# Sheet1.net
KiCad netlist of a schematic drawn in Altium Designer
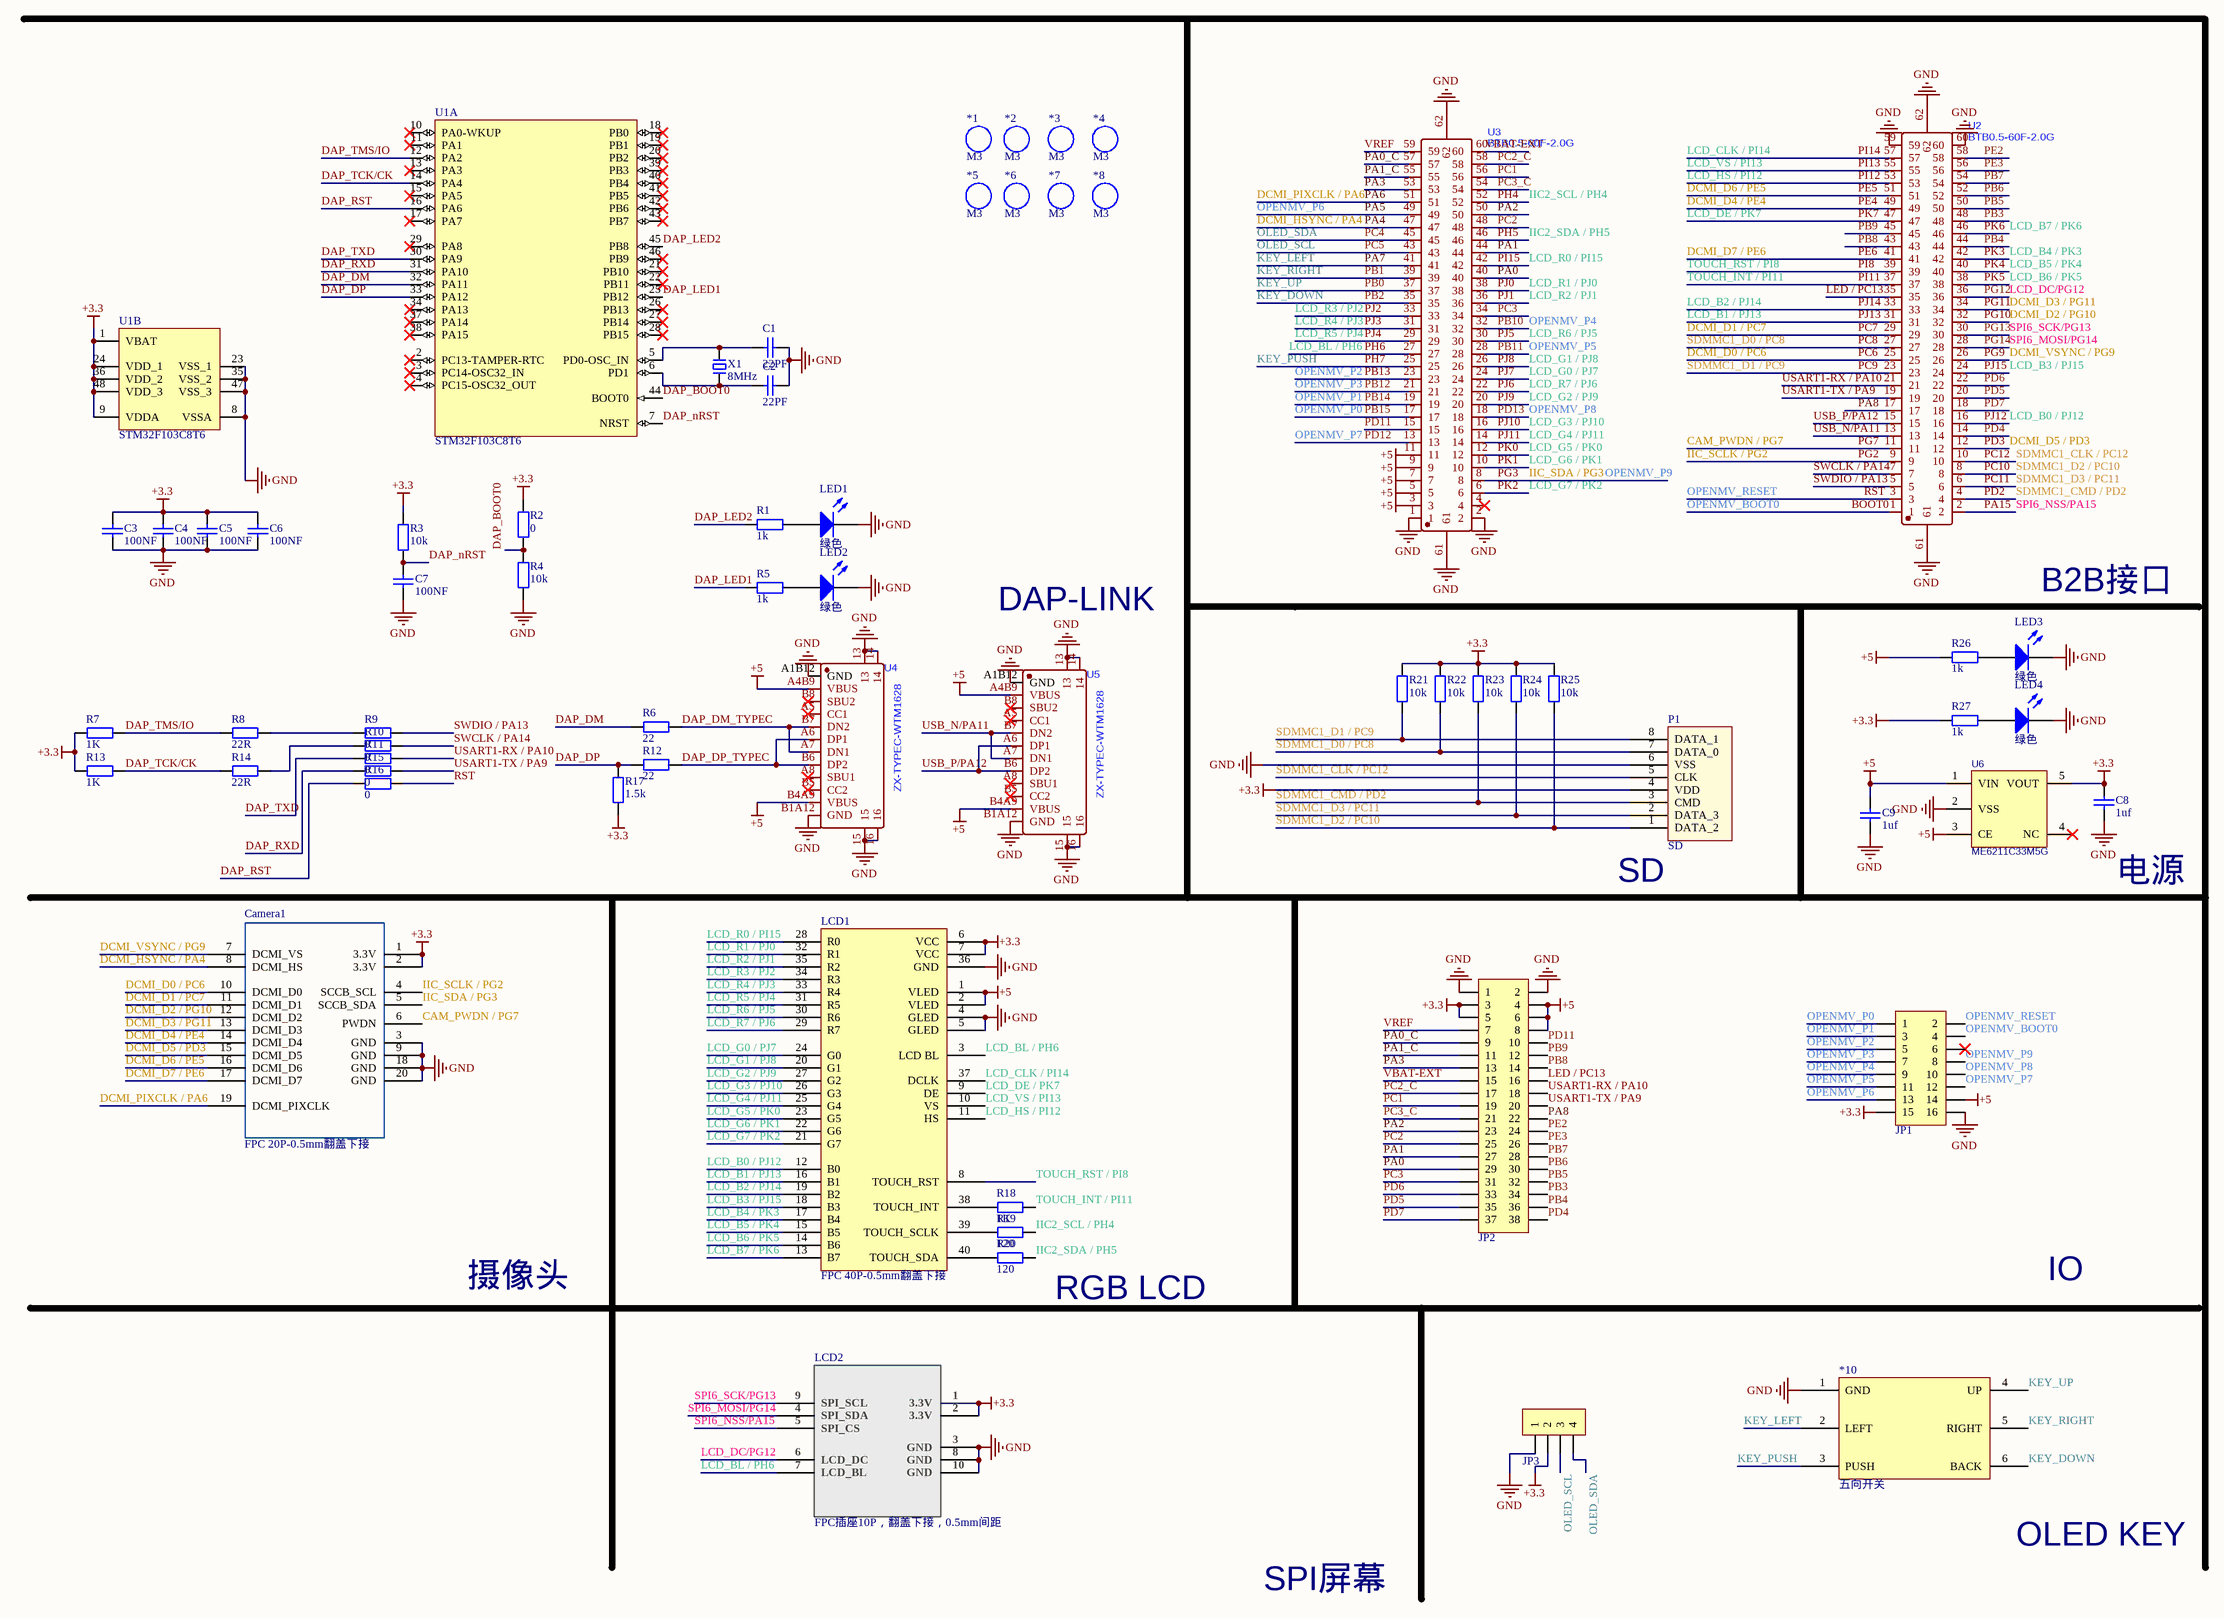
[diagram p0: Sheet1.SchDoc]

(export (version "E")
  (design (tool "Eeschema 10.0.6"))
  (components
    (comp (ref "*1")
      (value "M3")
      (footprint "PCB1:M3 125X200")
      (description "铜柱孔")
      (libsource (lib "STM32H750底板") (part "M3"))
    )
    (comp (ref "*2")
      (value "M3")
      (footprint "PCB1:M3 125X200")
      (description "铜柱孔")
      (libsource (lib "STM32H750底板") (part "M3"))
    )
    (comp (ref "*3")
      (value "M3")
      (footprint "PCB1:M3 125X200")
      (description "铜柱孔")
      (libsource (lib "STM32H750底板") (part "M3"))
    )
    (comp (ref "*4")
      (value "M3")
      (footprint "PCB1:M3 125X200")
      (description "铜柱孔")
      (libsource (lib "STM32H750底板") (part "M3"))
    )
    (comp (ref "*5")
      (value "M3")
      (footprint "PCB1:M3 125X200")
      (description "铜柱孔")
      (libsource (lib "STM32H750底板") (part "M3"))
    )
    (comp (ref "*6")
      (value "M3")
      (footprint "PCB1:M3 125X200")
      (description "铜柱孔")
      (libsource (lib "STM32H750底板") (part "M3"))
    )
    (comp (ref "*7")
      (value "M3")
      (footprint "PCB1:M3 125X200")
      (description "铜柱孔")
      (libsource (lib "STM32H750底板") (part "M3"))
    )
    (comp (ref "*8")
      (value "M3")
      (footprint "PCB1:M3 125X200")
      (description "铜柱孔")
      (libsource (lib "STM32H750底板") (part "M3"))
    )
    (comp (ref "*10")
      (value "五向开关")
      (footprint "PCB1:PCBComponent_1 - duplicate")
      (libsource (lib "STM32H750底板") (part "五向开关"))
    )
    (comp (ref "C1")
      (value "22PF")
      (footprint "PCB1:C0603_L")
      (description "贴片电容/MLCC电容")
      (libsource (lib "STM32H750底板") (part "C"))
    )
    (comp (ref "C2")
      (value "22PF")
      (footprint "PCB1:C0603_L")
      (description "贴片电容/MLCC电容")
      (libsource (lib "STM32H750底板") (part "C"))
    )
    (comp (ref "C3")
      (value "100NF")
      (footprint "PCB1:C0603_L")
      (description "贴片电容/MLCC电容")
      (libsource (lib "STM32H750底板") (part "C"))
    )
    (comp (ref "C4")
      (value "100NF")
      (footprint "PCB1:C0603_L")
      (description "贴片电容/MLCC电容")
      (libsource (lib "STM32H750底板") (part "C"))
    )
    (comp (ref "C5")
      (value "100NF")
      (footprint "PCB1:C0603_L")
      (description "贴片电容/MLCC电容")
      (libsource (lib "STM32H750底板") (part "C"))
    )
    (comp (ref "C6")
      (value "100NF")
      (footprint "PCB1:C0603_L")
      (description "贴片电容/MLCC电容")
      (libsource (lib "STM32H750底板") (part "C"))
    )
    (comp (ref "C7")
      (value "100NF")
      (footprint "PCB1:C0603_L")
      (description "贴片电容/MLCC电容")
      (libsource (lib "STM32H750底板") (part "C"))
    )
    (comp (ref "C8")
      (value "1uf")
      (footprint "PCB1:C0603_L")
      (description "贴片电容/MLCC电容")
      (libsource (lib "STM32H750底板") (part "C"))
    )
    (comp (ref "C9")
      (value "1uf")
      (footprint "PCB1:C0603_L")
      (description "贴片电容/MLCC电容")
      (libsource (lib "STM32H750底板") (part "C"))
    )
    (comp (ref "Camera1")
      (value "FPC 20P-0.5mm翻盖下接")
      (footprint "PCB1:FPC20P-0.5MM")
      (libsource (lib "STM32H750底板") (part "FK_Camera"))
    )
    (comp (ref "JP1")
      (value "Header 8X2")
      (footprint "PCB1:HDR2.54-LI-2x8P")
      (description "8*2P接插件")
      (libsource (lib "STM32H750底板") (part "Header 8X2"))
    )
    (comp (ref "JP2")
      (value "Header 2X11")
      (footprint "PCB1:HDR2.54-LI-2x19P")
      (description "19*2P接插件")
      (libsource (lib "STM32H750底板") (part "Header 19X2"))
    )
    (comp (ref "JP3")
      (value "HDR-1X4")
      (footprint "PCB1:HDR2.54-LI-4P")
      (description "4P接插件")
      (libsource (lib "STM32H750底板") (part "Header 4"))
    )
    (comp (ref "LCD1")
      (value "FPC 40P-0.5mm翻盖下接")
      (footprint "PCB1:FPC40P-0.5MM")
      (libsource (lib "STM32H750底板") (part "MY-RGB"))
    )
    (comp (ref "LCD2")
      (value "FPC插座10P，翻盖下接，0.5mm间距")
      (footprint "PCB1:FPC10P-0.5MM")
      (libsource (lib "STM32H750底板") (part "LCD-SPI"))
    )
    (comp (ref "LED1")
      (value "绿色")
      (footprint "PCB1:LED0805_G")
      (description "贴片LED")
      (libsource (lib "STM32H750底板") (part "LED"))
    )
    (comp (ref "LED2")
      (value "绿色")
      (footprint "PCB1:LED0805_G")
      (description "贴片LED")
      (libsource (lib "STM32H750底板") (part "LED"))
    )
    (comp (ref "LED3")
      (value "绿色")
      (footprint "PCB1:LED0805_G")
      (description "贴片LED")
      (libsource (lib "STM32H750底板") (part "LED"))
    )
    (comp (ref "LED4")
      (value "绿色")
      (footprint "PCB1:LED0805_G")
      (description "贴片LED")
      (libsource (lib "STM32H750底板") (part "LED"))
    )
    (comp (ref "P1")
      (value "SD")
      (footprint "PCB1:MICRO SD")
      (description "自弹式TF卡座")
      (libsource (lib "STM32H750底板") (part "Micro SD_SD"))
    )
    (comp (ref "R1")
      (value "1k")
      (footprint "PCB1:R0603_L")
      (description "贴片电阻")
      (libsource (lib "STM32H750底板") (part "R"))
    )
    (comp (ref "R2")
      (value "0")
      (footprint "PCB1:R0603_L")
      (description "贴片电阻")
      (libsource (lib "STM32H750底板") (part "R"))
    )
    (comp (ref "R3")
      (value "10k")
      (footprint "PCB1:R0603_L")
      (description "贴片电阻")
      (libsource (lib "STM32H750底板") (part "R"))
    )
    (comp (ref "R4")
      (value "10k")
      (footprint "PCB1:R0603_L")
      (description "贴片电阻")
      (libsource (lib "STM32H750底板") (part "R"))
    )
    (comp (ref "R5")
      (value "1k")
      (footprint "PCB1:R0603_L")
      (description "贴片电阻")
      (libsource (lib "STM32H750底板") (part "R"))
    )
    (comp (ref "R6")
      (value "22")
      (footprint "PCB1:R0402_L")
      (description "贴片电阻")
      (libsource (lib "STM32H750底板") (part "R"))
    )
    (comp (ref "R7")
      (value "1K")
      (footprint "PCB1:R0603_L")
      (description "贴片电阻")
      (libsource (lib "STM32H750底板") (part "R"))
    )
    (comp (ref "R8")
      (value "22R")
      (footprint "PCB1:R0603_L")
      (description "贴片电阻")
      (libsource (lib "STM32H750底板") (part "R"))
    )
    (comp (ref "R9")
      (value "0")
      (footprint "PCB1:R0603_L")
      (description "贴片电阻")
      (libsource (lib "STM32H750底板") (part "R"))
    )
    (comp (ref "R10")
      (value "0")
      (footprint "PCB1:R0603_L")
      (description "贴片电阻")
      (libsource (lib "STM32H750底板") (part "R"))
    )
    (comp (ref "R11")
      (value "0")
      (footprint "PCB1:R0603_L")
      (description "贴片电阻")
      (libsource (lib "STM32H750底板") (part "R"))
    )
    (comp (ref "R12")
      (value "22")
      (footprint "PCB1:R0402_L")
      (description "贴片电阻")
      (libsource (lib "STM32H750底板") (part "R"))
    )
    (comp (ref "R13")
      (value "1K")
      (footprint "PCB1:R0603_L")
      (description "贴片电阻")
      (libsource (lib "STM32H750底板") (part "R"))
    )
    (comp (ref "R14")
      (value "22R")
      (footprint "PCB1:R0603_L")
      (description "贴片电阻")
      (libsource (lib "STM32H750底板") (part "R"))
    )
    (comp (ref "R15")
      (value "0")
      (footprint "PCB1:R0603_L")
      (description "贴片电阻")
      (libsource (lib "STM32H750底板") (part "R"))
    )
    (comp (ref "R16")
      (value "0")
      (footprint "PCB1:R0603_L")
      (description "贴片电阻")
      (libsource (lib "STM32H750底板") (part "R"))
    )
    (comp (ref "R17")
      (value "1.5k")
      (footprint "PCB1:R0402_L")
      (description "贴片电阻")
      (libsource (lib "STM32H750底板") (part "R"))
    )
    (comp (ref "R18")
      (value "1K")
      (footprint "PCB1:R0603_L")
      (description "贴片电阻")
      (libsource (lib "STM32H750底板") (part "R"))
    )
    (comp (ref "R19")
      (value "120")
      (footprint "PCB1:R0603_L")
      (description "贴片电阻")
      (libsource (lib "STM32H750底板") (part "R"))
    )
    (comp (ref "R20")
      (value "120")
      (footprint "PCB1:R0603_L")
      (description "贴片电阻")
      (libsource (lib "STM32H750底板") (part "R"))
    )
    (comp (ref "R21")
      (value "10k")
      (footprint "PCB1:R0603_L")
      (description "贴片电阻")
      (libsource (lib "STM32H750底板") (part "R"))
    )
    (comp (ref "R22")
      (value "10k")
      (footprint "PCB1:R0603_L")
      (description "贴片电阻")
      (libsource (lib "STM32H750底板") (part "R"))
    )
    (comp (ref "R23")
      (value "10k")
      (footprint "PCB1:R0603_L")
      (description "贴片电阻")
      (libsource (lib "STM32H750底板") (part "R"))
    )
    (comp (ref "R24")
      (value "10k")
      (footprint "PCB1:R0603_L")
      (description "贴片电阻")
      (libsource (lib "STM32H750底板") (part "R"))
    )
    (comp (ref "R25")
      (value "10k")
      (footprint "PCB1:R0603_L")
      (description "贴片电阻")
      (libsource (lib "STM32H750底板") (part "R"))
    )
    (comp (ref "R26")
      (value "1k")
      (footprint "PCB1:R0603_L")
      (description "贴片电阻")
      (libsource (lib "STM32H750底板") (part "R"))
    )
    (comp (ref "R27")
      (value "1k")
      (footprint "PCB1:R0603_L")
      (description "贴片电阻")
      (libsource (lib "STM32H750底板") (part "R"))
    )
    (comp (ref "U1")
      (value "STM32F103C8T6")
      (footprint "PCB1:LQFP48_N")
      (libsource (lib "STM32H750底板") (part "STM32F103C8T6"))
    )
    (comp (ref "U2")
      (value "BTB0.5-60F-2.0G")
      (footprint "PCB1:CONN-SMD_60P-P0.50_BTB0.5-60F-2.0G")
      (libsource (lib "STM32H750底板") (part "BTB0.5-60F-2.0G"))
    )
    (comp (ref "U3")
      (value "BTB0.5-60F-2.0G")
      (footprint "PCB1:CONN-SMD_60P-P0.50_BTB0.5-60F-2.0G")
      (libsource (lib "STM32H750底板") (part "BTB0.5-60F-2.0G"))
    )
    (comp (ref "U4")
      (value "ZX-TYPEC-WTM1628")
      (footprint "PCB1:USB-C-SMD_ZX-TYPEC-WTM1628")
      (libsource (lib "STM32H750底板") (part "ZX-TYPEC-WTM1628"))
    )
    (comp (ref "U5")
      (value "ZX-TYPEC-WTM1628")
      (footprint "PCB1:USB-C-SMD_ZX-TYPEC-WTM1628")
      (libsource (lib "STM32H750底板") (part "ZX-TYPEC-WTM1628"))
    )
    (comp (ref "U6")
      (value "ME6211C33M5G")
      (footprint "PCB1:SOT-23-5")
      (description "LDO 3.3V/0.5A")
      (libsource (lib "STM32H750底板") (part "ME6211C33"))
    )
    (comp (ref "X1")
      (value "8MHz")
      (footprint "PCB1:XTAL-3215-2P")
      (description "2脚无源晶振(谐振器）")
      (libsource (lib "STM32H750底板") (part "XTAL-2P"))
    )
  )
  (nets
    (net (code "1") (name "+3.3") (class "Default")
      (node (ref "C3") (pin "2") (pinfunction "2_2") (pintype "passive"))
      (node (ref "C4") (pin "2") (pinfunction "2_2") (pintype "passive"))
      (node (ref "C5") (pin "2") (pinfunction "2_2") (pintype "passive"))
      (node (ref "C6") (pin "2") (pinfunction "2_2") (pintype "passive"))
      (node (ref "C8") (pin "2") (pinfunction "2_2") (pintype "passive"))
      (node (ref "Camera1") (pin "1") (pinfunction "3.3V_1") (pintype "passive"))
      (node (ref "Camera1") (pin "2") (pinfunction "3.3V_2") (pintype "passive"))
      (node (ref "JP1") (pin "15") (pinfunction "15_15") (pintype "passive"))
      (node (ref "JP2") (pin "3") (pinfunction "3_3") (pintype "passive"))
      (node (ref "JP2") (pin "5") (pinfunction "5_5") (pintype "passive"))
      (node (ref "JP3") (pin "2") (pinfunction "2_2") (pintype "passive"))
      (node (ref "LCD1") (pin "6") (pinfunction "VCC_6") (pintype "passive"))
      (node (ref "LCD1") (pin "7") (pinfunction "VCC_7") (pintype "passive"))
      (node (ref "LCD2") (pin "1") (pinfunction "3.3V_1") (pintype "passive"))
      (node (ref "LCD2") (pin "2") (pinfunction "3.3V_2") (pintype "passive"))
      (node (ref "P1") (pin "4") (pinfunction "VDD_4") (pintype "passive"))
      (node (ref "R13") (pin "1") (pinfunction "1_1") (pintype "passive"))
      (node (ref "R17") (pin "1") (pinfunction "1_1") (pintype "passive"))
      (node (ref "R2") (pin "2") (pinfunction "2_2") (pintype "passive"))
      (node (ref "R21") (pin "1") (pinfunction "1_1") (pintype "passive"))
      (node (ref "R22") (pin "1") (pinfunction "1_1") (pintype "passive"))
      (node (ref "R23") (pin "1") (pinfunction "1_1") (pintype "passive"))
      (node (ref "R24") (pin "1") (pinfunction "1_1") (pintype "passive"))
      (node (ref "R25") (pin "1") (pinfunction "1_1") (pintype "passive"))
      (node (ref "R27") (pin "1") (pinfunction "1_1") (pintype "passive"))
      (node (ref "R3") (pin "2") (pinfunction "2_2") (pintype "passive"))
      (node (ref "R7") (pin "1") (pinfunction "1_1") (pintype "passive"))
      (node (ref "U1") (pin "1") (pinfunction "VBAT_1") (pintype "power_in"))
      (node (ref "U1") (pin "24") (pinfunction "VDD_1_24") (pintype "power_in"))
      (node (ref "U1") (pin "36") (pinfunction "VDD_2_36") (pintype "power_in"))
      (node (ref "U1") (pin "48") (pinfunction "VDD_3_48") (pintype "power_in"))
      (node (ref "U1") (pin "9") (pinfunction "VDDA_9") (pintype "power_in"))
      (node (ref "U6") (pin "5") (pinfunction "VOUT_5") (pintype "passive"))
    )
    (net (code "2") (name "+5") (class "Default")
      (node (ref "C9") (pin "2") (pinfunction "2_2") (pintype "passive"))
      (node (ref "JP1") (pin "14") (pinfunction "14_14") (pintype "passive"))
      (node (ref "JP2") (pin "4") (pinfunction "4_4") (pintype "passive"))
      (node (ref "JP2") (pin "6") (pinfunction "6_6") (pintype "passive"))
      (node (ref "JP2") (pin "8") (pinfunction "8_8") (pintype "passive"))
      (node (ref "LCD1") (pin "1") (pinfunction "VLED_1") (pintype "passive"))
      (node (ref "LCD1") (pin "2") (pinfunction "VLED_2") (pintype "passive"))
      (node (ref "R26") (pin "1") (pinfunction "1_1") (pintype "passive"))
      (node (ref "U3") (pin "11") (pinfunction "11_11") (pintype "passive"))
      (node (ref "U3") (pin "3") (pinfunction "3_3") (pintype "passive"))
      (node (ref "U3") (pin "5") (pinfunction "5_5") (pintype "passive"))
      (node (ref "U3") (pin "7") (pinfunction "7_7") (pintype "passive"))
      (node (ref "U3") (pin "9") (pinfunction "9_9") (pintype "passive"))
      (node (ref "U4") (pin "A4B9") (pinfunction "VBUS_A4B9") (pintype "passive"))
      (node (ref "U4") (pin "B4A9") (pinfunction "VBUS_B4A9") (pintype "passive"))
      (node (ref "U5") (pin "A4B9") (pinfunction "VBUS_A4B9") (pintype "passive"))
      (node (ref "U5") (pin "B4A9") (pinfunction "VBUS_B4A9") (pintype "passive"))
      (node (ref "U6") (pin "1") (pinfunction "VIN_1") (pintype "passive"))
      (node (ref "U6") (pin "3") (pinfunction "CE_3") (pintype "passive"))
    )
    (net (code "3") (name "/BOOT0") (class "Default")
      (node (ref "JP1") (pin "4") (pinfunction "4_4") (pintype "passive"))
      (node (ref "U2") (pin "1") (pinfunction "1_1") (pintype "passive"))
    )
    (net (code "4") (name "/CAM_PWDN {slash} PG7") (class "Default")
      (node (ref "Camera1") (pin "6") (pinfunction "PWDN_6") (pintype "passive"))
      (node (ref "U2") (pin "11") (pinfunction "11_11") (pintype "passive"))
    )
    (net (code "5") (name "/DAP_BOOT0") (class "Default")
      (node (ref "R2") (pin "1") (pinfunction "1_1") (pintype "passive"))
      (node (ref "R4") (pin "2") (pinfunction "2_2") (pintype "passive"))
      (node (ref "U1") (pin "44") (pinfunction "BOOT0_44") (pintype "input"))
    )
    (net (code "6") (name "/DAP_DM") (class "Default")
      (node (ref "R6") (pin "1") (pinfunction "1_1") (pintype "passive"))
      (node (ref "U1") (pin "32") (pinfunction "PA11_32") (pintype "bidirectional"))
    )
    (net (code "7") (name "/DAP_DM_TYPEC") (class "Default")
      (node (ref "R6") (pin "2") (pinfunction "2_2") (pintype "passive"))
      (node (ref "U4") (pin "A7") (pinfunction "DN1_A7") (pintype "passive"))
      (node (ref "U4") (pin "B7") (pinfunction "DN2_B7") (pintype "passive"))
    )
    (net (code "8") (name "/DAP_DP") (class "Default")
      (node (ref "R12") (pin "1") (pinfunction "1_1") (pintype "passive"))
      (node (ref "R17") (pin "2") (pinfunction "2_2") (pintype "passive"))
      (node (ref "U1") (pin "33") (pinfunction "PA12_33") (pintype "bidirectional"))
    )
    (net (code "9") (name "/DAP_DP_TYPEC") (class "Default")
      (node (ref "R12") (pin "2") (pinfunction "2_2") (pintype "passive"))
      (node (ref "U4") (pin "A6") (pinfunction "DP1_A6") (pintype "passive"))
      (node (ref "U4") (pin "B6") (pinfunction "DP2_B6") (pintype "passive"))
    )
    (net (code "10") (name "/DAP_LED1") (class "Default")
      (node (ref "R5") (pin "1") (pinfunction "1_1") (pintype "passive"))
      (node (ref "U1") (pin "25") (pinfunction "PB12_25") (pintype "bidirectional"))
    )
    (net (code "11") (name "/DAP_LED2") (class "Default")
      (node (ref "R1") (pin "1") (pinfunction "1_1") (pintype "passive"))
      (node (ref "U1") (pin "45") (pinfunction "PB8_45") (pintype "bidirectional"))
    )
    (net (code "12") (name "/DAP_RST") (class "Default")
      (node (ref "R16") (pin "1") (pinfunction "1_1") (pintype "passive"))
      (node (ref "U1") (pin "16") (pinfunction "PA6_16") (pintype "bidirectional"))
    )
    (net (code "13") (name "/DAP_RXD") (class "Default")
      (node (ref "R15") (pin "1") (pinfunction "1_1") (pintype "passive"))
      (node (ref "U1") (pin "31") (pinfunction "PA10_31") (pintype "bidirectional"))
    )
    (net (code "14") (name "/DAP_TCK{slash}CK") (class "Default")
      (node (ref "R13") (pin "2") (pinfunction "2_2") (pintype "passive"))
      (node (ref "R14") (pin "1") (pinfunction "1_1") (pintype "passive"))
      (node (ref "U1") (pin "14") (pinfunction "PA4_14") (pintype "bidirectional"))
    )
    (net (code "15") (name "/DAP_TMS{slash}IO") (class "Default")
      (node (ref "R7") (pin "2") (pinfunction "2_2") (pintype "passive"))
      (node (ref "R8") (pin "1") (pinfunction "1_1") (pintype "passive"))
      (node (ref "U1") (pin "12") (pinfunction "PA2_12") (pintype "bidirectional"))
    )
    (net (code "16") (name "/DAP_TXD") (class "Default")
      (node (ref "R11") (pin "1") (pinfunction "1_1") (pintype "passive"))
      (node (ref "U1") (pin "30") (pinfunction "PA9_30") (pintype "bidirectional"))
    )
    (net (code "17") (name "/DAP_nRST") (class "Default")
      (node (ref "C7") (pin "2") (pinfunction "2_2") (pintype "passive"))
      (node (ref "R3") (pin "1") (pinfunction "1_1") (pintype "passive"))
      (node (ref "U1") (pin "7") (pinfunction "NRST_7") (pintype "bidirectional"))
    )
    (net (code "18") (name "/DCMI_D0 {slash} PC6") (class "Default")
      (node (ref "Camera1") (pin "10") (pinfunction "DCMI_D0_10") (pintype "passive"))
      (node (ref "U2") (pin "25") (pinfunction "25_25") (pintype "passive"))
    )
    (net (code "19") (name "/DCMI_D1 {slash} PC7") (class "Default")
      (node (ref "Camera1") (pin "11") (pinfunction "DCMI_D1_11") (pintype "passive"))
      (node (ref "U2") (pin "29") (pinfunction "29_29") (pintype "passive"))
    )
    (net (code "20") (name "/DCMI_D2 {slash} PG10") (class "Default")
      (node (ref "Camera1") (pin "12") (pinfunction "DCMI_D2_12") (pintype "passive"))
      (node (ref "U2") (pin "32") (pinfunction "32_32") (pintype "passive"))
    )
    (net (code "21") (name "/DCMI_D3 {slash} PG11") (class "Default")
      (node (ref "Camera1") (pin "13") (pinfunction "DCMI_D3_13") (pintype "passive"))
      (node (ref "U2") (pin "34") (pinfunction "34_34") (pintype "passive"))
    )
    (net (code "22") (name "/DCMI_D4 {slash} PE4") (class "Default")
      (node (ref "Camera1") (pin "14") (pinfunction "DCMI_D4_14") (pintype "passive"))
      (node (ref "U2") (pin "49") (pinfunction "49_49") (pintype "passive"))
    )
    (net (code "23") (name "/DCMI_D5 {slash} PD3") (class "Default")
      (node (ref "Camera1") (pin "15") (pinfunction "DCMI_D5_15") (pintype "passive"))
      (node (ref "U2") (pin "12") (pinfunction "12_12") (pintype "passive"))
    )
    (net (code "24") (name "/DCMI_D6 {slash} PE5") (class "Default")
      (node (ref "Camera1") (pin "16") (pinfunction "DCMI_D6_16") (pintype "passive"))
      (node (ref "U2") (pin "51") (pinfunction "51_51") (pintype "passive"))
    )
    (net (code "25") (name "/DCMI_D7 {slash} PE6") (class "Default")
      (node (ref "Camera1") (pin "17") (pinfunction "DCMI_D7_17") (pintype "passive"))
      (node (ref "U2") (pin "41") (pinfunction "41_41") (pintype "passive"))
    )
    (net (code "26") (name "/DCMI_HSYNC {slash} PA4") (class "Default")
      (node (ref "Camera1") (pin "8") (pinfunction "DCMI_HS_8") (pintype "passive"))
      (node (ref "U3") (pin "47") (pinfunction "47_47") (pintype "passive"))
    )
    (net (code "27") (name "/DCMI_PIXCLK {slash} PA6") (class "Default")
      (node (ref "Camera1") (pin "19") (pinfunction "DCMI_PIXCLK_19") (pintype "passive"))
      (node (ref "U3") (pin "51") (pinfunction "51_51") (pintype "passive"))
    )
    (net (code "28") (name "/DCMI_VSYNC {slash} PG9") (class "Default")
      (node (ref "Camera1") (pin "7") (pinfunction "DCMI_VS_7") (pintype "passive"))
      (node (ref "U2") (pin "26") (pinfunction "26_26") (pintype "passive"))
    )
    (net (code "29") (name "/IIC2_SCL {slash} PH4") (class "Default")
      (node (ref "R19") (pin "2") (pinfunction "2_2") (pintype "passive"))
      (node (ref "U3") (pin "52") (pinfunction "52_52") (pintype "passive"))
    )
    (net (code "30") (name "/IIC2_SDA {slash} PH5") (class "Default")
      (node (ref "R20") (pin "2") (pinfunction "2_2") (pintype "passive"))
      (node (ref "U3") (pin "46") (pinfunction "46_46") (pintype "passive"))
    )
    (net (code "31") (name "/IIC_SCLK {slash} PG2") (class "Default")
      (node (ref "Camera1") (pin "4") (pinfunction "SCCB_SCL_4") (pintype "passive"))
      (node (ref "U2") (pin "9") (pinfunction "9_9") (pintype "passive"))
    )
    (net (code "32") (name "/IIC_SDA {slash} PG3") (class "Default")
      (node (ref "Camera1") (pin "5") (pinfunction "SCCB_SDA_5") (pintype "passive"))
      (node (ref "JP1") (pin "8") (pinfunction "8_8") (pintype "passive"))
      (node (ref "U3") (pin "8") (pinfunction "8_8") (pintype "passive"))
    )
    (net (code "33") (name "/KEY_DOWN") (class "Default")
      (node (ref "*10") (pin "6") (pinfunction "BACK_6") (pintype "passive"))
      (node (ref "U3") (pin "35") (pinfunction "35_35") (pintype "passive"))
    )
    (net (code "34") (name "/KEY_LEFT") (class "Default")
      (node (ref "*10") (pin "2") (pinfunction "LEFT_2") (pintype "passive"))
      (node (ref "U3") (pin "41") (pinfunction "41_41") (pintype "passive"))
    )
    (net (code "35") (name "/KEY_PUSH") (class "Default")
      (node (ref "*10") (pin "3") (pinfunction "PUSH_3") (pintype "passive"))
      (node (ref "U3") (pin "25") (pinfunction "25_25") (pintype "passive"))
    )
    (net (code "36") (name "/KEY_RIGHT") (class "Default")
      (node (ref "*10") (pin "5") (pinfunction "RIGHT_5") (pintype "passive"))
      (node (ref "U3") (pin "39") (pinfunction "39_39") (pintype "passive"))
    )
    (net (code "37") (name "/KEY_UP") (class "Default")
      (node (ref "*10") (pin "4") (pinfunction "UP_4") (pintype "passive"))
      (node (ref "U3") (pin "37") (pinfunction "37_37") (pintype "passive"))
    )
    (net (code "38") (name "/LCD_B0 {slash} PJ12") (class "Default")
      (node (ref "LCD1") (pin "12") (pinfunction "B0_12") (pintype "passive"))
      (node (ref "U2") (pin "16") (pinfunction "16_16") (pintype "passive"))
    )
    (net (code "39") (name "/LCD_B1 {slash} PJ13") (class "Default")
      (node (ref "LCD1") (pin "16") (pinfunction "B1_16") (pintype "passive"))
      (node (ref "U2") (pin "31") (pinfunction "31_31") (pintype "passive"))
    )
    (net (code "40") (name "/LCD_B2 {slash} PJ14") (class "Default")
      (node (ref "LCD1") (pin "19") (pinfunction "B2_19") (pintype "passive"))
      (node (ref "U2") (pin "33") (pinfunction "33_33") (pintype "passive"))
    )
    (net (code "41") (name "/LCD_B3 {slash} PJ15") (class "Default")
      (node (ref "LCD1") (pin "18") (pinfunction "B3_18") (pintype "passive"))
      (node (ref "U2") (pin "24") (pinfunction "24_24") (pintype "passive"))
    )
    (net (code "42") (name "/LCD_B4 {slash} PK3") (class "Default")
      (node (ref "LCD1") (pin "17") (pinfunction "B4_17") (pintype "passive"))
      (node (ref "U2") (pin "42") (pinfunction "42_42") (pintype "passive"))
    )
    (net (code "43") (name "/LCD_B5 {slash} PK4") (class "Default")
      (node (ref "LCD1") (pin "15") (pinfunction "B5_15") (pintype "passive"))
      (node (ref "U2") (pin "40") (pinfunction "40_40") (pintype "passive"))
    )
    (net (code "44") (name "/LCD_B6 {slash} PK5") (class "Default")
      (node (ref "LCD1") (pin "14") (pinfunction "B6_14") (pintype "passive"))
      (node (ref "U2") (pin "38") (pinfunction "38_38") (pintype "passive"))
    )
    (net (code "45") (name "/LCD_B7 {slash} PK6") (class "Default")
      (node (ref "LCD1") (pin "13") (pinfunction "B7_13") (pintype "passive"))
      (node (ref "U2") (pin "46") (pinfunction "46_46") (pintype "passive"))
    )
    (net (code "46") (name "/LCD_BL {slash} PH6") (class "Default")
      (node (ref "LCD1") (pin "3") (pinfunction "LCD_BL_3") (pintype "passive"))
      (node (ref "LCD2") (pin "7") (pinfunction "LCD_BL_7") (pintype "passive"))
      (node (ref "U3") (pin "27") (pinfunction "27_27") (pintype "passive"))
    )
    (net (code "47") (name "/LCD_CLK {slash} PI14") (class "Default")
      (node (ref "LCD1") (pin "37") (pinfunction "DCLK_37") (pintype "passive"))
      (node (ref "U2") (pin "57") (pinfunction "57_57") (pintype "passive"))
    )
    (net (code "48") (name "/LCD_DC{slash}PG12") (class "Default")
      (node (ref "LCD2") (pin "6") (pinfunction "LCD_DC_6") (pintype "passive"))
      (node (ref "U2") (pin "36") (pinfunction "36_36") (pintype "passive"))
    )
    (net (code "49") (name "/LCD_DE {slash} PK7") (class "Default")
      (node (ref "LCD1") (pin "9") (pinfunction "DE_9") (pintype "passive"))
      (node (ref "U2") (pin "47") (pinfunction "47_47") (pintype "passive"))
    )
    (net (code "50") (name "/LCD_G0 {slash} PJ7") (class "Default")
      (node (ref "LCD1") (pin "24") (pinfunction "G0_24") (pintype "passive"))
      (node (ref "U3") (pin "24") (pinfunction "24_24") (pintype "passive"))
    )
    (net (code "51") (name "/LCD_G1 {slash} PJ8") (class "Default")
      (node (ref "LCD1") (pin "20") (pinfunction "G1_20") (pintype "passive"))
      (node (ref "U3") (pin "26") (pinfunction "26_26") (pintype "passive"))
    )
    (net (code "52") (name "/LCD_G2 {slash} PJ9") (class "Default")
      (node (ref "LCD1") (pin "27") (pinfunction "G2_27") (pintype "passive"))
      (node (ref "U3") (pin "20") (pinfunction "20_20") (pintype "passive"))
    )
    (net (code "53") (name "/LCD_G3 {slash} PJ10") (class "Default")
      (node (ref "LCD1") (pin "26") (pinfunction "G3_26") (pintype "passive"))
      (node (ref "U3") (pin "16") (pinfunction "16_16") (pintype "passive"))
    )
    (net (code "54") (name "/LCD_G4 {slash} PJ11") (class "Default")
      (node (ref "LCD1") (pin "25") (pinfunction "G4_25") (pintype "passive"))
      (node (ref "U3") (pin "14") (pinfunction "14_14") (pintype "passive"))
    )
    (net (code "55") (name "/LCD_G5 {slash} PK0") (class "Default")
      (node (ref "LCD1") (pin "23") (pinfunction "G5_23") (pintype "passive"))
      (node (ref "U3") (pin "12") (pinfunction "12_12") (pintype "passive"))
    )
    (net (code "56") (name "/LCD_G6 {slash} PK1") (class "Default")
      (node (ref "LCD1") (pin "22") (pinfunction "G6_22") (pintype "passive"))
      (node (ref "U3") (pin "10") (pinfunction "10_10") (pintype "passive"))
    )
    (net (code "57") (name "/LCD_G7 {slash} PK2") (class "Default")
      (node (ref "LCD1") (pin "21") (pinfunction "G7_21") (pintype "passive"))
      (node (ref "U3") (pin "6") (pinfunction "6_6") (pintype "passive"))
    )
    (net (code "58") (name "/LCD_HS {slash} PI12") (class "Default")
      (node (ref "LCD1") (pin "11") (pinfunction "HS_11") (pintype "passive"))
      (node (ref "U2") (pin "53") (pinfunction "53_53") (pintype "passive"))
    )
    (net (code "59") (name "/LCD_R0 {slash} PI15") (class "Default")
      (node (ref "LCD1") (pin "28") (pinfunction "R0_28") (pintype "passive"))
      (node (ref "U3") (pin "42") (pinfunction "42_42") (pintype "passive"))
    )
    (net (code "60") (name "/LCD_R1 {slash} PJ0") (class "Default")
      (node (ref "LCD1") (pin "32") (pinfunction "R1_32") (pintype "passive"))
      (node (ref "U3") (pin "38") (pinfunction "38_38") (pintype "passive"))
    )
    (net (code "61") (name "/LCD_R2 {slash} PJ1") (class "Default")
      (node (ref "LCD1") (pin "35") (pinfunction "R2_35") (pintype "passive"))
      (node (ref "U3") (pin "36") (pinfunction "36_36") (pintype "passive"))
    )
    (net (code "62") (name "/LCD_R3 {slash} PJ2") (class "Default")
      (node (ref "LCD1") (pin "34") (pinfunction "R3_34") (pintype "passive"))
      (node (ref "U3") (pin "33") (pinfunction "33_33") (pintype "passive"))
    )
    (net (code "63") (name "/LCD_R4 {slash} PJ3") (class "Default")
      (node (ref "LCD1") (pin "33") (pinfunction "R4_33") (pintype "passive"))
      (node (ref "U3") (pin "31") (pinfunction "31_31") (pintype "passive"))
    )
    (net (code "64") (name "/LCD_R5 {slash} PJ4") (class "Default")
      (node (ref "LCD1") (pin "31") (pinfunction "R5_31") (pintype "passive"))
      (node (ref "U3") (pin "29") (pinfunction "29_29") (pintype "passive"))
    )
    (net (code "65") (name "/LCD_R6 {slash} PJ5") (class "Default")
      (node (ref "LCD1") (pin "30") (pinfunction "R6_30") (pintype "passive"))
      (node (ref "U3") (pin "30") (pinfunction "30_30") (pintype "passive"))
    )
    (net (code "66") (name "/LCD_R7 {slash} PJ6") (class "Default")
      (node (ref "LCD1") (pin "29") (pinfunction "R7_29") (pintype "passive"))
      (node (ref "U3") (pin "22") (pinfunction "22_22") (pintype "passive"))
    )
    (net (code "67") (name "/LCD_VS {slash} PI13") (class "Default")
      (node (ref "LCD1") (pin "10") (pinfunction "VS_10") (pintype "passive"))
      (node (ref "U2") (pin "55") (pinfunction "55_55") (pintype "passive"))
    )
    (net (code "68") (name "/LED {slash} PC13") (class "Default")
      (node (ref "JP2") (pin "16") (pinfunction "16_16") (pintype "passive"))
      (node (ref "U2") (pin "35") (pinfunction "35_35") (pintype "passive"))
    )
    (net (code "69") (name "/OLED_SCL") (class "Default")
      (node (ref "JP3") (pin "3") (pinfunction "3_3") (pintype "passive"))
      (node (ref "U3") (pin "43") (pinfunction "43_43") (pintype "passive"))
    )
    (net (code "70") (name "/OLED_SDA") (class "Default")
      (node (ref "JP3") (pin "4") (pinfunction "4_4") (pintype "passive"))
      (node (ref "U3") (pin "45") (pinfunction "45_45") (pintype "passive"))
    )
    (net (code "71") (name "/OPENMV_P0") (class "Default")
      (node (ref "JP1") (pin "1") (pinfunction "1_1") (pintype "passive"))
      (node (ref "U3") (pin "17") (pinfunction "17_17") (pintype "passive"))
    )
    (net (code "72") (name "/OPENMV_P1") (class "Default")
      (node (ref "JP1") (pin "3") (pinfunction "3_3") (pintype "passive"))
      (node (ref "U3") (pin "19") (pinfunction "19_19") (pintype "passive"))
    )
    (net (code "73") (name "/OPENMV_P2") (class "Default")
      (node (ref "JP1") (pin "5") (pinfunction "5_5") (pintype "passive"))
      (node (ref "U3") (pin "23") (pinfunction "23_23") (pintype "passive"))
    )
    (net (code "74") (name "/OPENMV_P3") (class "Default")
      (node (ref "JP1") (pin "7") (pinfunction "7_7") (pintype "passive"))
      (node (ref "U3") (pin "21") (pinfunction "21_21") (pintype "passive"))
    )
    (net (code "75") (name "/OPENMV_P4") (class "Default")
      (node (ref "JP1") (pin "9") (pinfunction "9_9") (pintype "passive"))
      (node (ref "U3") (pin "32") (pinfunction "32_32") (pintype "passive"))
    )
    (net (code "76") (name "/OPENMV_P5") (class "Default")
      (node (ref "JP1") (pin "11") (pinfunction "11_11") (pintype "passive"))
      (node (ref "U3") (pin "28") (pinfunction "28_28") (pintype "passive"))
    )
    (net (code "77") (name "/OPENMV_P6") (class "Default")
      (node (ref "JP1") (pin "13") (pinfunction "13_13") (pintype "passive"))
      (node (ref "U3") (pin "49") (pinfunction "49_49") (pintype "passive"))
    )
    (net (code "78") (name "/OPENMV_P7") (class "Default")
      (node (ref "JP1") (pin "12") (pinfunction "12_12") (pintype "passive"))
      (node (ref "U3") (pin "13") (pinfunction "13_13") (pintype "passive"))
    )
    (net (code "79") (name "/OPENMV_P8") (class "Default")
      (node (ref "JP1") (pin "10") (pinfunction "10_10") (pintype "passive"))
      (node (ref "U3") (pin "18") (pinfunction "18_18") (pintype "passive"))
    )
    (net (code "80") (name "/OPENMV_RESET") (class "Default")
      (node (ref "JP1") (pin "2") (pinfunction "2_2") (pintype "passive"))
      (node (ref "R16") (pin "2") (pinfunction "2_2") (pintype "passive"))
      (node (ref "U2") (pin "3") (pinfunction "3_3") (pintype "passive"))
    )
    (net (code "81") (name "/PA0") (class "Default")
      (node (ref "JP2") (pin "29") (pinfunction "29_29") (pintype "passive"))
      (node (ref "U3") (pin "40") (pinfunction "40_40") (pintype "passive"))
    )
    (net (code "82") (name "/PA0_C") (class "Default")
      (node (ref "JP2") (pin "9") (pinfunction "9_9") (pintype "passive"))
      (node (ref "U3") (pin "57") (pinfunction "57_57") (pintype "passive"))
    )
    (net (code "83") (name "/PA1") (class "Default")
      (node (ref "JP2") (pin "27") (pinfunction "27_27") (pintype "passive"))
      (node (ref "U3") (pin "44") (pinfunction "44_44") (pintype "passive"))
    )
    (net (code "84") (name "/PA1_C") (class "Default")
      (node (ref "JP2") (pin "11") (pinfunction "11_11") (pintype "passive"))
      (node (ref "U3") (pin "55") (pinfunction "55_55") (pintype "passive"))
    )
    (net (code "85") (name "/PA2") (class "Default")
      (node (ref "JP2") (pin "23") (pinfunction "23_23") (pintype "passive"))
      (node (ref "U3") (pin "50") (pinfunction "50_50") (pintype "passive"))
    )
    (net (code "86") (name "/PA3") (class "Default")
      (node (ref "JP2") (pin "13") (pinfunction "13_13") (pintype "passive"))
      (node (ref "U3") (pin "53") (pinfunction "53_53") (pintype "passive"))
    )
    (net (code "87") (name "/PA8") (class "Default")
      (node (ref "JP2") (pin "22") (pinfunction "22_22") (pintype "passive"))
      (node (ref "U2") (pin "17") (pinfunction "17_17") (pintype "passive"))
    )
    (net (code "88") (name "/PA15") (class "Default")
      (node (ref "LCD2") (pin "5") (pinfunction "SPI_CS_5") (pintype "passive"))
      (node (ref "U2") (pin "2") (pinfunction "2_2") (pintype "passive"))
    )
    (net (code "89") (name "/PB3") (class "Default")
      (node (ref "JP2") (pin "34") (pinfunction "34_34") (pintype "passive"))
      (node (ref "U2") (pin "48") (pinfunction "48_48") (pintype "passive"))
    )
    (net (code "90") (name "/PB4") (class "Default")
      (node (ref "JP2") (pin "36") (pinfunction "36_36") (pintype "passive"))
      (node (ref "U2") (pin "44") (pinfunction "44_44") (pintype "passive"))
    )
    (net (code "91") (name "/PB5") (class "Default")
      (node (ref "JP2") (pin "32") (pinfunction "32_32") (pintype "passive"))
      (node (ref "U2") (pin "50") (pinfunction "50_50") (pintype "passive"))
    )
    (net (code "92") (name "/PB6") (class "Default")
      (node (ref "JP2") (pin "30") (pinfunction "30_30") (pintype "passive"))
      (node (ref "U2") (pin "52") (pinfunction "52_52") (pintype "passive"))
    )
    (net (code "93") (name "/PB7") (class "Default")
      (node (ref "JP2") (pin "28") (pinfunction "28_28") (pintype "passive"))
      (node (ref "U2") (pin "54") (pinfunction "54_54") (pintype "passive"))
    )
    (net (code "94") (name "/PB8") (class "Default")
      (node (ref "JP2") (pin "14") (pinfunction "14_14") (pintype "passive"))
      (node (ref "U2") (pin "43") (pinfunction "43_43") (pintype "passive"))
    )
    (net (code "95") (name "/PB9") (class "Default")
      (node (ref "JP2") (pin "12") (pinfunction "12_12") (pintype "passive"))
      (node (ref "U2") (pin "45") (pinfunction "45_45") (pintype "passive"))
    )
    (net (code "96") (name "/PC1") (class "Default")
      (node (ref "JP2") (pin "19") (pinfunction "19_19") (pintype "passive"))
      (node (ref "U3") (pin "56") (pinfunction "56_56") (pintype "passive"))
    )
    (net (code "97") (name "/PC2") (class "Default")
      (node (ref "JP2") (pin "25") (pinfunction "25_25") (pintype "passive"))
      (node (ref "U3") (pin "48") (pinfunction "48_48") (pintype "passive"))
    )
    (net (code "98") (name "/PC2_C") (class "Default")
      (node (ref "JP2") (pin "17") (pinfunction "17_17") (pintype "passive"))
      (node (ref "U3") (pin "58") (pinfunction "58_58") (pintype "passive"))
    )
    (net (code "99") (name "/PC3") (class "Default")
      (node (ref "JP2") (pin "31") (pinfunction "31_31") (pintype "passive"))
      (node (ref "U3") (pin "34") (pinfunction "34_34") (pintype "passive"))
    )
    (net (code "100") (name "/PC3_C") (class "Default")
      (node (ref "JP2") (pin "21") (pinfunction "21_21") (pintype "passive"))
      (node (ref "U3") (pin "54") (pinfunction "54_54") (pintype "passive"))
    )
    (net (code "101") (name "/PC8") (class "Default")
      (node (ref "P1") (pin "7") (pinfunction "DATA_0_7") (pintype "passive"))
      (node (ref "R22") (pin "2") (pinfunction "2_2") (pintype "passive"))
      (node (ref "U2") (pin "27") (pinfunction "27_27") (pintype "passive"))
    )
    (net (code "102") (name "/PC9") (class "Default")
      (node (ref "P1") (pin "8") (pinfunction "DATA_1_8") (pintype "passive"))
      (node (ref "R21") (pin "2") (pinfunction "2_2") (pintype "passive"))
      (node (ref "U2") (pin "23") (pinfunction "23_23") (pintype "passive"))
    )
    (net (code "103") (name "/PC10") (class "Default")
      (node (ref "P1") (pin "1") (pinfunction "DATA_2_1") (pintype "passive"))
      (node (ref "R25") (pin "2") (pinfunction "2_2") (pintype "passive"))
      (node (ref "U2") (pin "8") (pinfunction "8_8") (pintype "passive"))
    )
    (net (code "104") (name "/PC11") (class "Default")
      (node (ref "P1") (pin "2") (pinfunction "DATA_3_2") (pintype "passive"))
      (node (ref "R24") (pin "2") (pinfunction "2_2") (pintype "passive"))
      (node (ref "U2") (pin "6") (pinfunction "6_6") (pintype "passive"))
    )
    (net (code "105") (name "/PC12") (class "Default")
      (node (ref "P1") (pin "5") (pinfunction "CLK_5") (pintype "passive"))
      (node (ref "U2") (pin "10") (pinfunction "10_10") (pintype "passive"))
    )
    (net (code "106") (name "/PD2") (class "Default")
      (node (ref "P1") (pin "3") (pinfunction "CMD_3") (pintype "passive"))
      (node (ref "R23") (pin "2") (pinfunction "2_2") (pintype "passive"))
      (node (ref "U2") (pin "4") (pinfunction "4_4") (pintype "passive"))
    )
    (net (code "107") (name "/PD4") (class "Default")
      (node (ref "JP2") (pin "38") (pinfunction "38_38") (pintype "passive"))
      (node (ref "U2") (pin "14") (pinfunction "14_14") (pintype "passive"))
    )
    (net (code "108") (name "/PD5") (class "Default")
      (node (ref "JP2") (pin "35") (pinfunction "35_35") (pintype "passive"))
      (node (ref "U2") (pin "20") (pinfunction "20_20") (pintype "passive"))
    )
    (net (code "109") (name "/PD6") (class "Default")
      (node (ref "JP2") (pin "33") (pinfunction "33_33") (pintype "passive"))
      (node (ref "U2") (pin "22") (pinfunction "22_22") (pintype "passive"))
    )
    (net (code "110") (name "/PD7") (class "Default")
      (node (ref "JP2") (pin "37") (pinfunction "37_37") (pintype "passive"))
      (node (ref "U2") (pin "18") (pinfunction "18_18") (pintype "passive"))
    )
    (net (code "111") (name "/PD11") (class "Default")
      (node (ref "JP2") (pin "10") (pinfunction "10_10") (pintype "passive"))
      (node (ref "U3") (pin "15") (pinfunction "15_15") (pintype "passive"))
    )
    (net (code "112") (name "/PE2") (class "Default")
      (node (ref "JP2") (pin "24") (pinfunction "24_24") (pintype "passive"))
      (node (ref "U2") (pin "58") (pinfunction "58_58") (pintype "passive"))
    )
    (net (code "113") (name "/PE3") (class "Default")
      (node (ref "JP2") (pin "26") (pinfunction "26_26") (pintype "passive"))
      (node (ref "U2") (pin "56") (pinfunction "56_56") (pintype "passive"))
    )
    (net (code "114") (name "/PG13") (class "Default")
      (node (ref "LCD2") (pin "9") (pinfunction "SPI_SCL_9") (pintype "passive"))
      (node (ref "U2") (pin "30") (pinfunction "30_30") (pintype "passive"))
    )
    (net (code "115") (name "/PG14") (class "Default")
      (node (ref "LCD2") (pin "4") (pinfunction "SPI_SDA_4") (pintype "passive"))
      (node (ref "U2") (pin "28") (pinfunction "28_28") (pintype "passive"))
    )
    (net (code "116") (name "/PI8") (class "Default")
      (node (ref "LCD1") (pin "8") (pinfunction "TOUCH_RST_8") (pintype "passive"))
      (node (ref "U2") (pin "39") (pinfunction "39_39") (pintype "passive"))
    )
    (net (code "117") (name "/PI11") (class "Default")
      (node (ref "R18") (pin "2") (pinfunction "2_2") (pintype "passive"))
      (node (ref "U2") (pin "37") (pinfunction "37_37") (pintype "passive"))
    )
    (net (code "118") (name "/SWCLK {slash} PA14") (class "Default")
      (node (ref "R10") (pin "2") (pinfunction "2_2") (pintype "passive"))
      (node (ref "U2") (pin "7") (pinfunction "7_7") (pintype "passive"))
    )
    (net (code "119") (name "/SWDIO {slash} PA13") (class "Default")
      (node (ref "R9") (pin "2") (pinfunction "2_2") (pintype "passive"))
      (node (ref "U2") (pin "5") (pinfunction "5_5") (pintype "passive"))
    )
    (net (code "120") (name "/USART1-RX {slash} PA10") (class "Default")
      (node (ref "JP2") (pin "18") (pinfunction "18_18") (pintype "passive"))
      (node (ref "R11") (pin "2") (pinfunction "2_2") (pintype "passive"))
      (node (ref "U2") (pin "21") (pinfunction "21_21") (pintype "passive"))
    )
    (net (code "121") (name "/USART1-TX {slash} PA9") (class "Default")
      (node (ref "JP2") (pin "20") (pinfunction "20_20") (pintype "passive"))
      (node (ref "R15") (pin "2") (pinfunction "2_2") (pintype "passive"))
      (node (ref "U2") (pin "19") (pinfunction "19_19") (pintype "passive"))
    )
    (net (code "122") (name "/USB_N{slash}PA11") (class "Default")
      (node (ref "U2") (pin "13") (pinfunction "13_13") (pintype "passive"))
      (node (ref "U5") (pin "A7") (pinfunction "DN1_A7") (pintype "passive"))
      (node (ref "U5") (pin "B7") (pinfunction "DN2_B7") (pintype "passive"))
    )
    (net (code "123") (name "/USB_P{slash}PA12") (class "Default")
      (node (ref "U2") (pin "15") (pinfunction "15_15") (pintype "passive"))
      (node (ref "U5") (pin "A6") (pinfunction "DP1_A6") (pintype "passive"))
      (node (ref "U5") (pin "B6") (pinfunction "DP2_B6") (pintype "passive"))
    )
    (net (code "124") (name "/VBAT-EXT") (class "Default")
      (node (ref "JP2") (pin "15") (pinfunction "15_15") (pintype "passive"))
      (node (ref "U3") (pin "60") (pinfunction "60_60") (pintype "passive"))
    )
    (net (code "125") (name "/VREF") (class "Default")
      (node (ref "JP2") (pin "7") (pinfunction "7_7") (pintype "passive"))
      (node (ref "U3") (pin "59") (pinfunction "59_59") (pintype "passive"))
    )
    (net (code "126") (name "GND") (class "Default")
      (node (ref "*10") (pin "1") (pinfunction "GND_1") (pintype "passive"))
      (node (ref "C1") (pin "2") (pinfunction "2_2") (pintype "passive"))
      (node (ref "C2") (pin "2") (pinfunction "2_2") (pintype "passive"))
      (node (ref "C3") (pin "1") (pinfunction "1_1") (pintype "passive"))
      (node (ref "C4") (pin "1") (pinfunction "1_1") (pintype "passive"))
      (node (ref "C5") (pin "1") (pinfunction "1_1") (pintype "passive"))
      (node (ref "C6") (pin "1") (pinfunction "1_1") (pintype "passive"))
      (node (ref "C7") (pin "1") (pinfunction "1_1") (pintype "passive"))
      (node (ref "C8") (pin "1") (pinfunction "1_1") (pintype "passive"))
      (node (ref "C9") (pin "1") (pinfunction "1_1") (pintype "passive"))
      (node (ref "Camera1") (pin "18") (pinfunction "GND_18") (pintype "passive"))
      (node (ref "Camera1") (pin "20") (pinfunction "GND_20") (pintype "passive"))
      (node (ref "Camera1") (pin "3") (pinfunction "GND_3") (pintype "passive"))
      (node (ref "Camera1") (pin "9") (pinfunction "GND_9") (pintype "passive"))
      (node (ref "JP1") (pin "16") (pinfunction "16_16") (pintype "passive"))
      (node (ref "JP2") (pin "1") (pinfunction "1_1") (pintype "passive"))
      (node (ref "JP2") (pin "2") (pinfunction "2_2") (pintype "passive"))
      (node (ref "JP3") (pin "1") (pinfunction "1_1") (pintype "passive"))
      (node (ref "LCD1") (pin "36") (pinfunction "GND_36") (pintype "passive"))
      (node (ref "LCD1") (pin "4") (pinfunction "GLED_4") (pintype "passive"))
      (node (ref "LCD1") (pin "5") (pinfunction "GLED_5") (pintype "passive"))
      (node (ref "LCD2") (pin "10") (pinfunction "GND_10") (pintype "passive"))
      (node (ref "LCD2") (pin "3") (pinfunction "GND_3") (pintype "passive"))
      (node (ref "LCD2") (pin "8") (pinfunction "GND_8") (pintype "passive"))
      (node (ref "LED1") (pin "2") (pinfunction "K_2") (pintype "passive"))
      (node (ref "LED2") (pin "2") (pinfunction "K_2") (pintype "passive"))
      (node (ref "LED3") (pin "2") (pinfunction "K_2") (pintype "passive"))
      (node (ref "LED4") (pin "2") (pinfunction "K_2") (pintype "passive"))
      (node (ref "P1") (pin "6") (pinfunction "VSS_6") (pintype "passive"))
      (node (ref "R4") (pin "1") (pinfunction "1_1") (pintype "passive"))
      (node (ref "U1") (pin "23") (pinfunction "VSS_1_23") (pintype "power_in"))
      (node (ref "U1") (pin "35") (pinfunction "VSS_2_35") (pintype "power_in"))
      (node (ref "U1") (pin "47") (pinfunction "VSS_3_47") (pintype "power_in"))
      (node (ref "U1") (pin "8") (pinfunction "VSSA_8") (pintype "power_in"))
      (node (ref "U2") (pin "59") (pinfunction "59_59") (pintype "passive"))
      (node (ref "U2") (pin "60") (pinfunction "60_60") (pintype "passive"))
      (node (ref "U2") (pin "61") (pinfunction "61_61") (pintype "passive"))
      (node (ref "U2") (pin "62") (pinfunction "62_62") (pintype "passive"))
      (node (ref "U3") (pin "1") (pinfunction "1_1") (pintype "passive"))
      (node (ref "U3") (pin "2") (pinfunction "2_2") (pintype "passive"))
      (node (ref "U3") (pin "61") (pinfunction "61_61") (pintype "passive"))
      (node (ref "U3") (pin "62") (pinfunction "62_62") (pintype "passive"))
      (node (ref "U4") (pin "13") (pinfunction "13_13") (pintype "passive"))
      (node (ref "U4") (pin "14") (pinfunction "14_14") (pintype "passive"))
      (node (ref "U4") (pin "15") (pinfunction "15_15") (pintype "passive"))
      (node (ref "U4") (pin "16") (pinfunction "16_16") (pintype "passive"))
      (node (ref "U4") (pin "A1B12") (pinfunction "GND_A1B12") (pintype "passive"))
      (node (ref "U4") (pin "B1A12") (pinfunction "GND_B1A12") (pintype "passive"))
      (node (ref "U5") (pin "13") (pinfunction "13_13") (pintype "passive"))
      (node (ref "U5") (pin "14") (pinfunction "14_14") (pintype "passive"))
      (node (ref "U5") (pin "15") (pinfunction "15_15") (pintype "passive"))
      (node (ref "U5") (pin "16") (pinfunction "16_16") (pintype "passive"))
      (node (ref "U5") (pin "A1B12") (pinfunction "GND_A1B12") (pintype "passive"))
      (node (ref "U5") (pin "B1A12") (pinfunction "GND_B1A12") (pintype "passive"))
      (node (ref "U6") (pin "2") (pinfunction "VSS_2") (pintype "passive"))
    )
    (net (code "127") (name "Net-(LCD1-TOUCH_INT)") (class "Default")
      (node (ref "LCD1") (pin "38") (pinfunction "TOUCH_INT_38") (pintype "passive"))
      (node (ref "R18") (pin "1") (pinfunction "1_1") (pintype "passive"))
    )
    (net (code "128") (name "Net-(LCD1-TOUCH_SCLK)") (class "Default")
      (node (ref "LCD1") (pin "39") (pinfunction "TOUCH_SCLK_39") (pintype "passive"))
      (node (ref "R19") (pin "1") (pinfunction "1_1") (pintype "passive"))
    )
    (net (code "129") (name "Net-(LCD1-TOUCH_SDA)") (class "Default")
      (node (ref "LCD1") (pin "40") (pinfunction "TOUCH_SDA_40") (pintype "passive"))
      (node (ref "R20") (pin "1") (pinfunction "1_1") (pintype "passive"))
    )
    (net (code "130") (name "Net-(LED1-A)") (class "Default")
      (node (ref "LED1") (pin "1") (pinfunction "A_1") (pintype "passive"))
      (node (ref "R1") (pin "2") (pinfunction "2_2") (pintype "passive"))
    )
    (net (code "131") (name "Net-(LED2-A)") (class "Default")
      (node (ref "LED2") (pin "1") (pinfunction "A_1") (pintype "passive"))
      (node (ref "R5") (pin "2") (pinfunction "2_2") (pintype "passive"))
    )
    (net (code "132") (name "Net-(LED3-A)") (class "Default")
      (node (ref "LED3") (pin "1") (pinfunction "A_1") (pintype "passive"))
      (node (ref "R26") (pin "2") (pinfunction "2_2") (pintype "passive"))
    )
    (net (code "133") (name "Net-(LED4-A)") (class "Default")
      (node (ref "LED4") (pin "1") (pinfunction "A_1") (pintype "passive"))
      (node (ref "R27") (pin "2") (pinfunction "2_2") (pintype "passive"))
    )
    (net (code "134") (name "Net-(R8-Pad2)") (class "Default")
      (node (ref "R8") (pin "2") (pinfunction "2_2") (pintype "passive"))
      (node (ref "R9") (pin "1") (pinfunction "1_1") (pintype "passive"))
    )
    (net (code "135") (name "Net-(R10-Pad1)") (class "Default")
      (node (ref "R10") (pin "1") (pinfunction "1_1") (pintype "passive"))
      (node (ref "R14") (pin "2") (pinfunction "2_2") (pintype "passive"))
    )
    (net (code "136") (name "Net-(U1A-PD0-OSC_IN)") (class "Default")
      (node (ref "C1") (pin "1") (pinfunction "1_1") (pintype "passive"))
      (node (ref "U1") (pin "5") (pinfunction "PD0-OSC_IN_5") (pintype "bidirectional"))
      (node (ref "X1") (pin "1") (pinfunction "1_1") (pintype "passive"))
    )
    (net (code "137") (name "Net-(U1A-PD1)") (class "Default")
      (node (ref "C2") (pin "1") (pinfunction "1_1") (pintype "passive"))
      (node (ref "U1") (pin "6") (pinfunction "PD1_6") (pintype "bidirectional"))
      (node (ref "X1") (pin "2") (pinfunction "2_2") (pintype "passive"))
    )
    (net (code "138") (name "unconnected-(JP1-Pad6)") (class "Default")
      (node (ref "JP1") (pin "6") (pinfunction "6_6") (pintype "passive+no_connect"))
    )
    (net (code "139") (name "unconnected-(U1A-PA0-WKUP-Pad10)") (class "Default")
      (node (ref "U1") (pin "10") (pinfunction "PA0-WKUP_10") (pintype "bidirectional+no_connect"))
    )
    (net (code "140") (name "unconnected-(U1A-PA1-Pad11)") (class "Default")
      (node (ref "U1") (pin "11") (pinfunction "PA1_11") (pintype "bidirectional+no_connect"))
    )
    (net (code "141") (name "unconnected-(U1A-PA3-Pad13)") (class "Default")
      (node (ref "U1") (pin "13") (pinfunction "PA3_13") (pintype "bidirectional+no_connect"))
    )
    (net (code "142") (name "unconnected-(U1A-PA5-Pad15)") (class "Default")
      (node (ref "U1") (pin "15") (pinfunction "PA5_15") (pintype "bidirectional+no_connect"))
    )
    (net (code "143") (name "unconnected-(U1A-PA7-Pad17)") (class "Default")
      (node (ref "U1") (pin "17") (pinfunction "PA7_17") (pintype "bidirectional+no_connect"))
    )
    (net (code "144") (name "unconnected-(U1A-PA8-Pad29)") (class "Default")
      (node (ref "U1") (pin "29") (pinfunction "PA8_29") (pintype "bidirectional+no_connect"))
    )
    (net (code "145") (name "unconnected-(U1A-PA13-Pad34)") (class "Default")
      (node (ref "U1") (pin "34") (pinfunction "PA13_34") (pintype "bidirectional+no_connect"))
    )
    (net (code "146") (name "unconnected-(U1A-PA14-Pad37)") (class "Default")
      (node (ref "U1") (pin "37") (pinfunction "PA14_37") (pintype "bidirectional+no_connect"))
    )
    (net (code "147") (name "unconnected-(U1A-PA15-Pad38)") (class "Default")
      (node (ref "U1") (pin "38") (pinfunction "PA15_38") (pintype "bidirectional+no_connect"))
    )
    (net (code "148") (name "unconnected-(U1A-PB0-Pad18)") (class "Default")
      (node (ref "U1") (pin "18") (pinfunction "PB0_18") (pintype "bidirectional+no_connect"))
    )
    (net (code "149") (name "unconnected-(U1A-PB1-Pad19)") (class "Default")
      (node (ref "U1") (pin "19") (pinfunction "PB1_19") (pintype "bidirectional+no_connect"))
    )
    (net (code "150") (name "unconnected-(U1A-PB2-Pad20)") (class "Default")
      (node (ref "U1") (pin "20") (pinfunction "PB2_20") (pintype "bidirectional+no_connect"))
    )
    (net (code "151") (name "unconnected-(U1A-PB3-Pad39)") (class "Default")
      (node (ref "U1") (pin "39") (pinfunction "PB3_39") (pintype "bidirectional+no_connect"))
    )
    (net (code "152") (name "unconnected-(U1A-PB4-Pad40)") (class "Default")
      (node (ref "U1") (pin "40") (pinfunction "PB4_40") (pintype "bidirectional+no_connect"))
    )
    (net (code "153") (name "unconnected-(U1A-PB5-Pad41)") (class "Default")
      (node (ref "U1") (pin "41") (pinfunction "PB5_41") (pintype "bidirectional+no_connect"))
    )
    (net (code "154") (name "unconnected-(U1A-PB6-Pad42)") (class "Default")
      (node (ref "U1") (pin "42") (pinfunction "PB6_42") (pintype "bidirectional+no_connect"))
    )
    (net (code "155") (name "unconnected-(U1A-PB7-Pad43)") (class "Default")
      (node (ref "U1") (pin "43") (pinfunction "PB7_43") (pintype "bidirectional+no_connect"))
    )
    (net (code "156") (name "unconnected-(U1A-PB9-Pad46)") (class "Default")
      (node (ref "U1") (pin "46") (pinfunction "PB9_46") (pintype "bidirectional+no_connect"))
    )
    (net (code "157") (name "unconnected-(U1A-PB10-Pad21)") (class "Default")
      (node (ref "U1") (pin "21") (pinfunction "PB10_21") (pintype "bidirectional+no_connect"))
    )
    (net (code "158") (name "unconnected-(U1A-PB11-Pad22)") (class "Default")
      (node (ref "U1") (pin "22") (pinfunction "PB11_22") (pintype "bidirectional+no_connect"))
    )
    (net (code "159") (name "unconnected-(U1A-PB13-Pad26)") (class "Default")
      (node (ref "U1") (pin "26") (pinfunction "PB13_26") (pintype "bidirectional+no_connect"))
    )
    (net (code "160") (name "unconnected-(U1A-PB14-Pad27)") (class "Default")
      (node (ref "U1") (pin "27") (pinfunction "PB14_27") (pintype "bidirectional+no_connect"))
    )
    (net (code "161") (name "unconnected-(U1A-PB15-Pad28)") (class "Default")
      (node (ref "U1") (pin "28") (pinfunction "PB15_28") (pintype "bidirectional+no_connect"))
    )
    (net (code "162") (name "unconnected-(U1A-PC13-TAMPER-RTC-Pad2)") (class "Default")
      (node (ref "U1") (pin "2") (pinfunction "PC13-TAMPER-RTC_2") (pintype "bidirectional+no_connect"))
    )
    (net (code "163") (name "unconnected-(U1A-PC14-OSC32_IN-Pad3)") (class "Default")
      (node (ref "U1") (pin "3") (pinfunction "PC14-OSC32_IN_3") (pintype "bidirectional+no_connect"))
    )
    (net (code "164") (name "unconnected-(U1A-PC15-OSC32_OUT-Pad4)") (class "Default")
      (node (ref "U1") (pin "4") (pinfunction "PC15-OSC32_OUT_4") (pintype "bidirectional+no_connect"))
    )
    (net (code "165") (name "unconnected-(U3-Pad4)") (class "Default")
      (node (ref "U3") (pin "4") (pinfunction "4_4") (pintype "passive+no_connect"))
    )
    (net (code "166") (name "unconnected-(U4-CC1-PadA5)") (class "Default")
      (node (ref "U4") (pin "A5") (pinfunction "CC1_A5") (pintype "passive+no_connect"))
    )
    (net (code "167") (name "unconnected-(U4-CC2-PadB5)") (class "Default")
      (node (ref "U4") (pin "B5") (pinfunction "CC2_B5") (pintype "passive+no_connect"))
    )
    (net (code "168") (name "unconnected-(U4-SBU1-PadA8)") (class "Default")
      (node (ref "U4") (pin "A8") (pinfunction "SBU1_A8") (pintype "passive+no_connect"))
    )
    (net (code "169") (name "unconnected-(U4-SBU2-PadB8)") (class "Default")
      (node (ref "U4") (pin "B8") (pinfunction "SBU2_B8") (pintype "passive+no_connect"))
    )
    (net (code "170") (name "unconnected-(U5-CC1-PadA5)") (class "Default")
      (node (ref "U5") (pin "A5") (pinfunction "CC1_A5") (pintype "passive+no_connect"))
    )
    (net (code "171") (name "unconnected-(U5-CC2-PadB5)") (class "Default")
      (node (ref "U5") (pin "B5") (pinfunction "CC2_B5") (pintype "passive+no_connect"))
    )
    (net (code "172") (name "unconnected-(U5-SBU1-PadA8)") (class "Default")
      (node (ref "U5") (pin "A8") (pinfunction "SBU1_A8") (pintype "passive+no_connect"))
    )
    (net (code "173") (name "unconnected-(U5-SBU2-PadB8)") (class "Default")
      (node (ref "U5") (pin "B8") (pinfunction "SBU2_B8") (pintype "passive+no_connect"))
    )
    (net (code "174") (name "unconnected-(U6-NC-Pad4)") (class "Default")
      (node (ref "U6") (pin "4") (pinfunction "NC_4") (pintype "passive+no_connect"))
    )
  )
)
